# Fri3D_IRA_Peripherals.net
KiCad netlist of a schematic drawn in Altium Designer
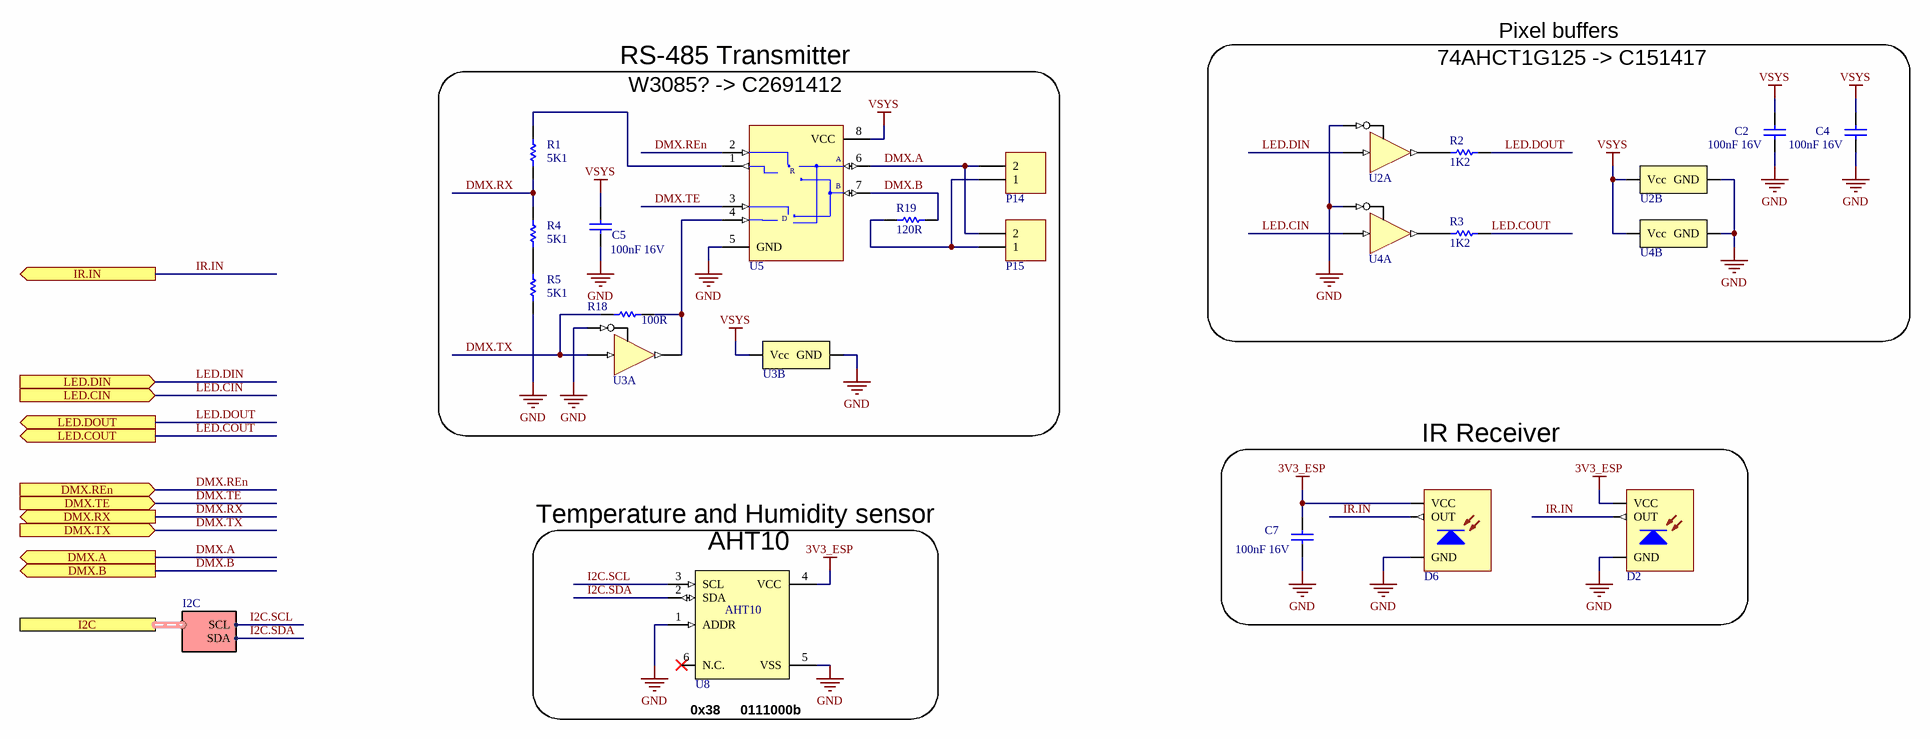
[diagram p0: Fri3D_IRA_Peripherals.SchDoc]

(export (version "E")
  (design (tool "Eeschema 10.0.6"))
  (components
    (comp (ref "C2")
      (value "100nF 16V")
      (footprint "C0603_N")
      (description "Capacitor Ceramic")
      (libsource (lib "Phyx_Components") (part "CAP_CERAMIC"))
    )
    (comp (ref "C4")
      (value "100nF 16V")
      (footprint "C0603_N")
      (description "Capacitor Ceramic")
      (libsource (lib "Phyx_Components") (part "CAP_CERAMIC"))
    )
    (comp (ref "C5")
      (value "100nF 16V")
      (footprint "C0603_N")
      (description "Capacitor Ceramic")
      (libsource (lib "Phyx_Components") (part "CAP_CERAMIC"))
    )
    (comp (ref "C7")
      (value "100nF 16V")
      (footprint "C0603_N")
      (description "Capacitor Ceramic")
      (libsource (lib "Phyx_Components") (part "CAP_CERAMIC"))
    )
    (comp (ref "D2")
      (value "ZIRM-5042B-42-Z2 Infrared Receiver 38 kHz 45° 2.7-5.5V 940nm")
      (footprint "CHAU_ZIRM-5042B-42-Z2")
      (description "=Description")
      (libsource (lib "Phyx_Components") (part "PHO_IR_TSOP381x"))
    )
    (comp (ref "D6")
      (value "IRM-3638N3F14 Infrared Receiver 38 kHz 45° 2.7-5.5V")
      (footprint "VIS_TSOP381x_BENT")
      (description "=Description")
      (libsource (lib "Phyx_Components") (part "PHO_IR_TSOP381x"))
    )
    (comp (ref "P14")
      (value "Easy to solder connection")
      (footprint "SOLDER_SW_V_1MM")
      (libsource (lib "Phyx_Components") (part "Header 2"))
    )
    (comp (ref "P15")
      (value "Header 2")
      (footprint "HDR1X2")
      (libsource (lib "Phyx_Components") (part "Header 2"))
    )
    (comp (ref "R1")
      (value "5K1")
      (footprint "R0603_N")
      (fields (field (name "Comment") "RESISTOR"))
      (libsource (lib "Phyx_Components") (part "RESISTOR"))
    )
    (comp (ref "R2")
      (value "1K2")
      (footprint "R0603_N")
      (fields (field (name "Comment") "RESISTOR"))
      (libsource (lib "Phyx_Components") (part "RESISTOR"))
    )
    (comp (ref "R3")
      (value "1K2")
      (footprint "R0603_N")
      (fields (field (name "Comment") "RESISTOR"))
      (libsource (lib "Phyx_Components") (part "RESISTOR"))
    )
    (comp (ref "R4")
      (value "5K1")
      (footprint "R0603_N")
      (fields (field (name "Comment") "RESISTOR"))
      (libsource (lib "Phyx_Components") (part "RESISTOR"))
    )
    (comp (ref "R5")
      (value "5K1")
      (footprint "R0603_N")
      (fields (field (name "Comment") "RESISTOR"))
      (libsource (lib "Phyx_Components") (part "RESISTOR"))
    )
    (comp (ref "R18")
      (value "100R")
      (footprint "R0603_N")
      (fields (field (name "Comment") "RESISTOR"))
      (libsource (lib "Phyx_Components") (part "RESISTOR"))
    )
    (comp (ref "R19")
      (value "120R")
      (footprint "R1206")
      (fields (field (name "Comment") "RESISTOR"))
      (libsource (lib "Phyx_Components") (part "RESISTOR"))
    )
    (comp (ref "U2")
      (value "SN74AHCT1G125DCKR  Buffer, Tri-State, 4.5V to 5.5V")
      (footprint "TI_DCK_R-PDSO-G5")
      (description "=Description")
      (libsource (lib "Phyx_Components") (part "SN74AHCT1G125"))
    )
    (comp (ref "U3")
      (value "SN74AHCT1G125DCKR  Buffer, Tri-State, 4.5V to 5.5V")
      (footprint "TI_DCK_R-PDSO-G5")
      (description "=Description")
      (libsource (lib "Phyx_Components") (part "SN74AHCT1G125"))
    )
    (comp (ref "U4")
      (value "SN74AHCT1G125DCKR  Buffer, Tri-State, 4.5V to 5.5V")
      (footprint "TI_DCK_R-PDSO-G5")
      (description "=Description")
      (libsource (lib "Phyx_Components") (part "SN74AHCT1G125"))
    )
    (comp (ref "U5")
      (value "RS-485 5V Transceiver")
      (footprint "SOIC_N_8")
      (libsource (lib "Phyx_Components") (part "MAX485"))
    )
    (comp (ref "U8")
      (value "AHT 10 Temperature and humidity sensor")
      (footprint "AHT10")
      (description "=Description")
      (libsource (lib "Phyx_Components") (part "AHT10"))
    )
  )
  (nets
    (net (code "2") (name "/DMX.A") (class "Default")
      (node (ref "P14") (pin "2") (pinfunction "2_2") (pintype "passive"))
      (node (ref "P15") (pin "2") (pinfunction "2_2") (pintype "passive"))
      (node (ref "U5") (pin "6") (pinfunction "A_6") (pintype "bidirectional"))
    )
    (net (code "3") (name "/DMX.B") (class "Default")
      (node (ref "R19") (pin "2") (pinfunction "2_2") (pintype "passive"))
      (node (ref "U5") (pin "7") (pinfunction "B_7") (pintype "bidirectional"))
    )
    (net (code "4") (name "/DMX.REn") (class "Default")
      (node (ref "U5") (pin "2") (pinfunction "~{RE}_2") (pintype "input"))
    )
    (net (code "5") (name "/DMX.RX") (class "Default")
      (node (ref "R1") (pin "2") (pinfunction "2_2") (pintype "passive"))
      (node (ref "R4") (pin "1") (pinfunction "1_1") (pintype "passive"))
    )
    (net (code "6") (name "/DMX.TE") (class "Default")
      (node (ref "U5") (pin "3") (pinfunction "DE_3") (pintype "input"))
    )
    (net (code "7") (name "/DMX.TX") (class "Default")
      (node (ref "R18") (pin "1") (pinfunction "1_1") (pintype "passive"))
      (node (ref "U3") (pin "2") (pinfunction "A_2") (pintype "input"))
    )
    (net (code "8") (name "/I2C.SCL") (class "Default")
      (node (ref "U8") (pin "3") (pinfunction "SCL_3") (pintype "input"))
    )
    (net (code "9") (name "/I2C.SDA") (class "Default")
      (node (ref "U8") (pin "2") (pinfunction "SDA_2") (pintype "bidirectional"))
    )
    (net (code "10") (name "/IR.IN") (class "Default")
      (node (ref "D2") (pin "1") (pinfunction "OUT_1") (pintype "output"))
      (node (ref "D6") (pin "1") (pinfunction "OUT_1") (pintype "output"))
    )
    (net (code "11") (name "/LED.CIN") (class "Default")
      (node (ref "U4") (pin "2") (pinfunction "A_2") (pintype "input"))
    )
    (net (code "12") (name "/LED.COUT") (class "Default")
      (node (ref "R3") (pin "2") (pinfunction "2_2") (pintype "passive"))
    )
    (net (code "13") (name "/LED.DIN") (class "Default")
      (node (ref "U2") (pin "2") (pinfunction "A_2") (pintype "input"))
    )
    (net (code "14") (name "/LED.DOUT") (class "Default")
      (node (ref "R2") (pin "2") (pinfunction "2_2") (pintype "passive"))
    )
    (net (code "16") (name "3V3_ESP") (class "Default")
      (node (ref "C7") (pin "1") (pinfunction "1_1") (pintype "passive"))
      (node (ref "D2") (pin "3") (pinfunction "VCC_3") (pintype "power_in"))
      (node (ref "D6") (pin "3") (pinfunction "VCC_3") (pintype "power_in"))
      (node (ref "U8") (pin "4") (pinfunction "VCC_4") (pintype "power_in"))
    )
    (net (code "17") (name "GND") (class "Default")
      (node (ref "C2") (pin "2") (pinfunction "2_2") (pintype "passive"))
      (node (ref "C4") (pin "2") (pinfunction "2_2") (pintype "passive"))
      (node (ref "C5") (pin "2") (pinfunction "2_2") (pintype "passive"))
      (node (ref "C7") (pin "2") (pinfunction "2_2") (pintype "passive"))
      (node (ref "D2") (pin "2") (pinfunction "GND_2") (pintype "power_in"))
      (node (ref "D6") (pin "2") (pinfunction "GND_2") (pintype "power_in"))
      (node (ref "R5") (pin "2") (pinfunction "2_2") (pintype "passive"))
      (node (ref "U2") (pin "1") (pinfunction "~{OE}_1") (pintype "input"))
      (node (ref "U2") (pin "3") (pinfunction "GND_3") (pintype "power_in"))
      (node (ref "U3") (pin "1") (pinfunction "~{OE}_1") (pintype "input"))
      (node (ref "U3") (pin "3") (pinfunction "GND_3") (pintype "power_in"))
      (node (ref "U4") (pin "1") (pinfunction "~{OE}_1") (pintype "input"))
      (node (ref "U4") (pin "3") (pinfunction "GND_3") (pintype "power_in"))
      (node (ref "U5") (pin "5") (pinfunction "GND_5") (pintype "power_in"))
      (node (ref "U8") (pin "1") (pinfunction "ADDR_1") (pintype "input"))
      (node (ref "U8") (pin "5") (pinfunction "VSS_5") (pintype "power_in"))
    )
    (net (code "18") (name "Net-(P14-Pad1)") (class "Default")
      (node (ref "P14") (pin "1") (pinfunction "1_1") (pintype "passive"))
      (node (ref "P15") (pin "1") (pinfunction "1_1") (pintype "passive"))
      (node (ref "R19") (pin "1") (pinfunction "1_1") (pintype "passive"))
    )
    (net (code "19") (name "Net-(R4-Pad2)") (class "Default")
      (node (ref "R4") (pin "2") (pinfunction "2_2") (pintype "passive"))
      (node (ref "R5") (pin "1") (pinfunction "1_1") (pintype "passive"))
    )
    (net (code "20") (name "Net-(U2A-Y)") (class "Default")
      (node (ref "R2") (pin "1") (pinfunction "1_1") (pintype "passive"))
      (node (ref "U2") (pin "4") (pinfunction "Y_4") (pintype "output"))
    )
    (net (code "21") (name "Net-(U3A-Y)") (class "Default")
      (node (ref "R18") (pin "2") (pinfunction "2_2") (pintype "passive"))
      (node (ref "U3") (pin "4") (pinfunction "Y_4") (pintype "output"))
      (node (ref "U5") (pin "4") (pinfunction "DI_4") (pintype "input"))
    )
    (net (code "22") (name "Net-(U4A-Y)") (class "Default")
      (node (ref "R3") (pin "1") (pinfunction "1_1") (pintype "passive"))
      (node (ref "U4") (pin "4") (pinfunction "Y_4") (pintype "output"))
    )
    (net (code "23") (name "Net-(U5-RO)") (class "Default")
      (node (ref "R1") (pin "1") (pinfunction "1_1") (pintype "passive"))
      (node (ref "U5") (pin "1") (pinfunction "RO_1") (pintype "output"))
    )
    (net (code "24") (name "VSYS") (class "Default")
      (node (ref "C2") (pin "1") (pinfunction "1_1") (pintype "passive"))
      (node (ref "C4") (pin "1") (pinfunction "1_1") (pintype "passive"))
      (node (ref "C5") (pin "1") (pinfunction "1_1") (pintype "passive"))
      (node (ref "U2") (pin "5") (pinfunction "Vcc_5") (pintype "power_in"))
      (node (ref "U3") (pin "5") (pinfunction "Vcc_5") (pintype "power_in"))
      (node (ref "U4") (pin "5") (pinfunction "Vcc_5") (pintype "power_in"))
      (node (ref "U5") (pin "8") (pinfunction "VCC_8") (pintype "power_in"))
    )
    (net (code "25") (name "unconnected-(U8-N.C.-Pad6)") (class "Default")
      (node (ref "U8") (pin "6") (pinfunction "N.C._6") (pintype "passive+no_connect"))
    )
  )
)
